# current_probe.net
KiCad netlist of a schematic drawn in EAGLE
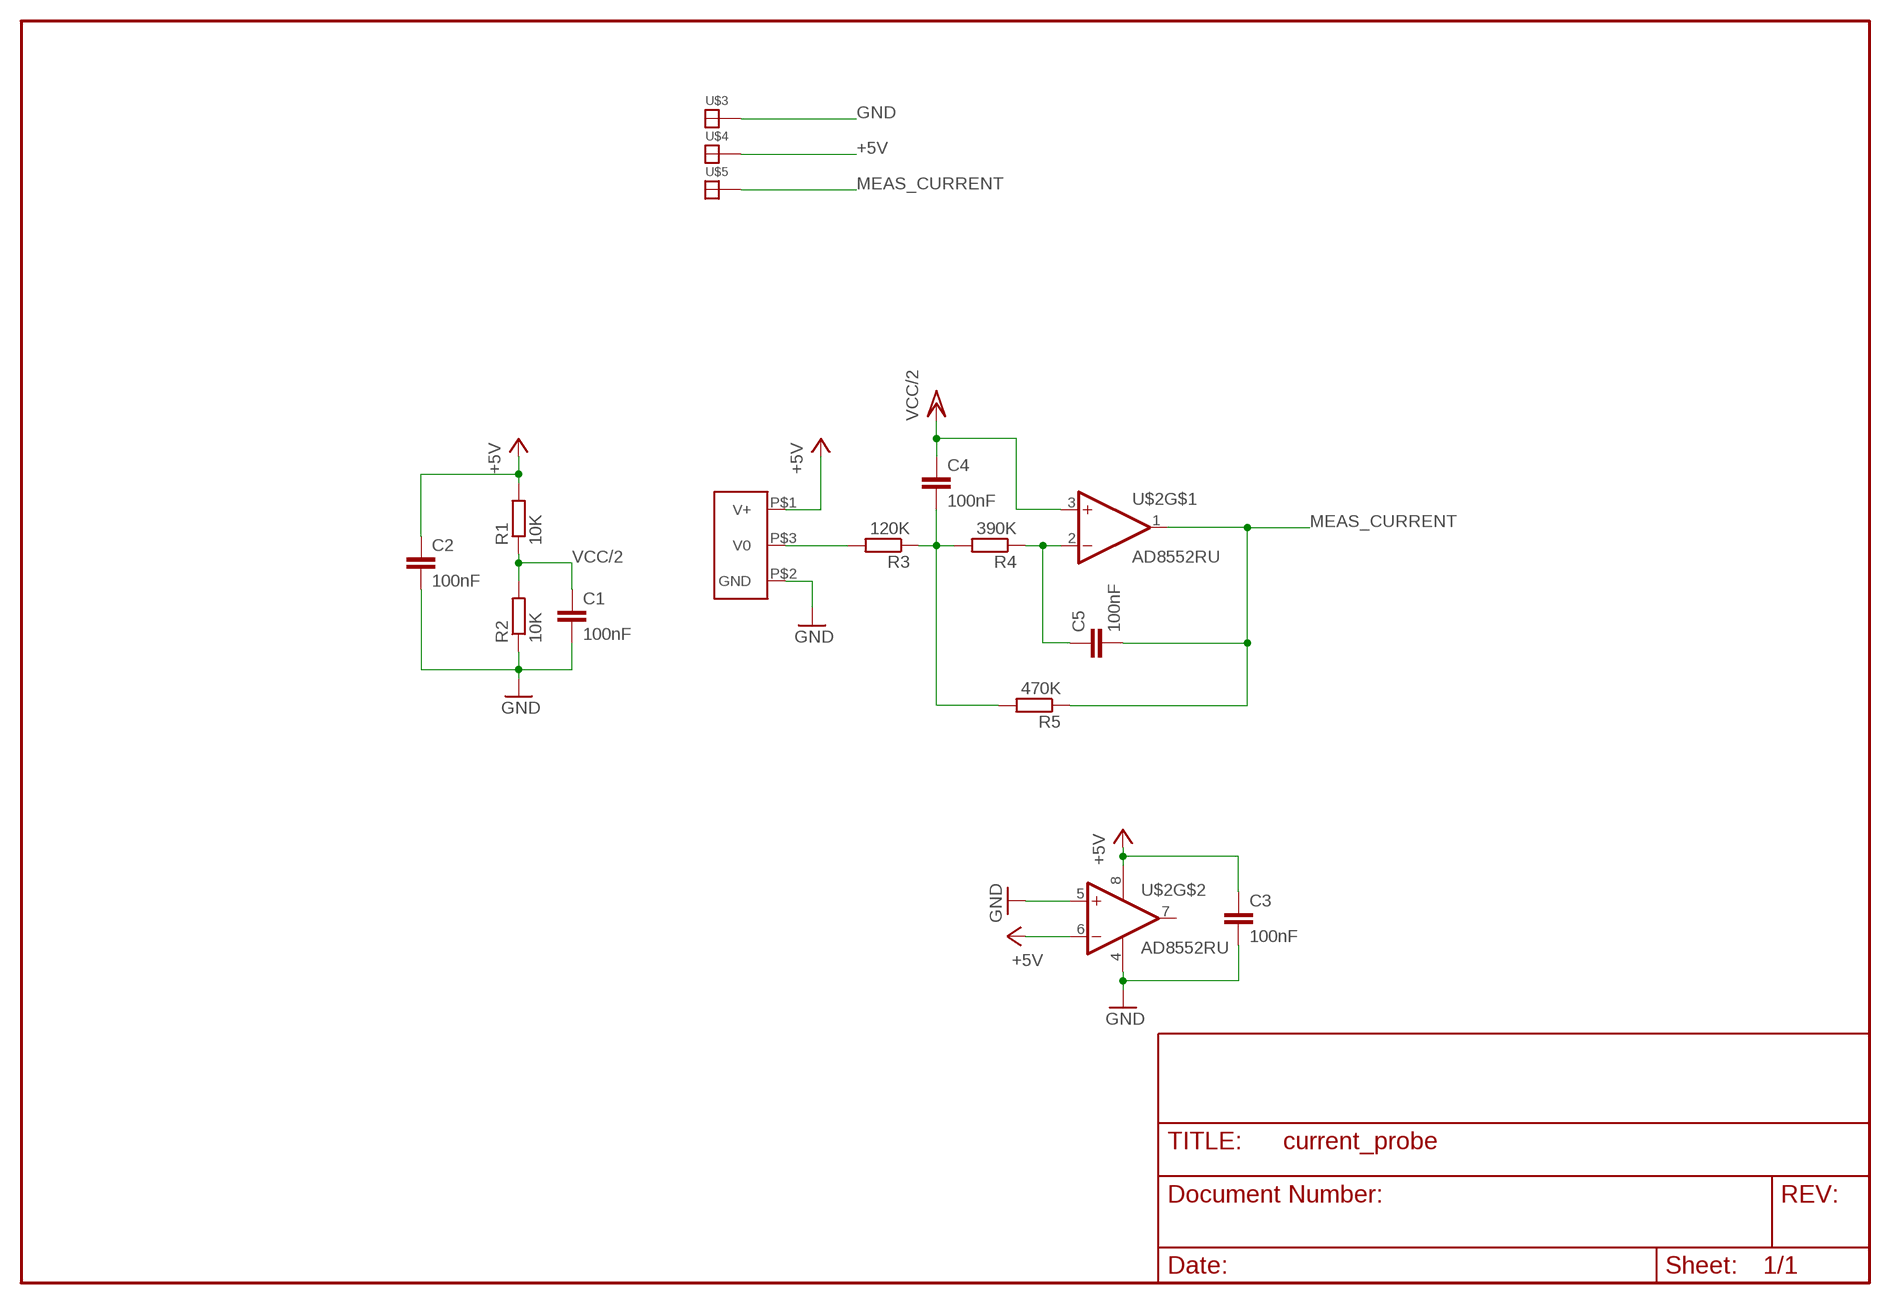
[diagram p0: schematic, sheet 1]

(export (version "E")
  (design (tool "Eeschema 10.0.6"))
  (components
    (comp (ref "C1")
      (value "100nF")
      (footprint "eagle-import:C0603K")
      (libsource (lib "eagle-import") (part "C-EUC0603K"))
    )
    (comp (ref "C2")
      (value "100nF")
      (footprint "eagle-import:C0603K")
      (libsource (lib "eagle-import") (part "C-EUC0603K"))
    )
    (comp (ref "C3")
      (value "100nF")
      (footprint "eagle-import:C0603K")
      (libsource (lib "eagle-import") (part "C-EUC0603K"))
    )
    (comp (ref "C4")
      (value "100nF")
      (footprint "eagle-import:C0603K")
      (libsource (lib "eagle-import") (part "C-EUC0603K"))
    )
    (comp (ref "C5")
      (value "100nF")
      (footprint "eagle-import:C0603K")
      (libsource (lib "eagle-import") (part "C-EUC0603K"))
    )
    (comp (ref "R1")
      (value "10K")
      (footprint "eagle-import:R0603")
      (libsource (lib "eagle-import") (part "R-EU_R0603"))
    )
    (comp (ref "R2")
      (value "10K")
      (footprint "eagle-import:R0603")
      (libsource (lib "eagle-import") (part "R-EU_R0603"))
    )
    (comp (ref "R3")
      (value "120K")
      (footprint "eagle-import:R0603")
      (libsource (lib "eagle-import") (part "R-EU_R0603"))
    )
    (comp (ref "R4")
      (value "390K")
      (footprint "eagle-import:R0603")
      (libsource (lib "eagle-import") (part "R-EU_R0603"))
    )
    (comp (ref "R5")
      (value "470K")
      (footprint "eagle-import:R0603")
      (libsource (lib "eagle-import") (part "R-EU_R0603"))
    )
    (comp (ref "U$1")
      (value "SS495S")
      (footprint "eagle-import:SS495SND")
      (libsource (lib "eagle-import") (part "SS495S"))
    )
    (comp (ref "U$2")
      (value "AD8552RU")
      (footprint "eagle-import:TSSOP8")
      (libsource (lib "eagle-import") (part "AD8552RU"))
    )
    (comp (ref "U$3")
      (value "SOLDER_PAD100_50")
      (footprint "eagle-import:SOLDER_PAD_100_50")
      (libsource (lib "eagle-import") (part "SOLDER_PAD100_50"))
    )
    (comp (ref "U$4")
      (value "SOLDER_PAD100_50")
      (footprint "eagle-import:SOLDER_PAD_100_50")
      (libsource (lib "eagle-import") (part "SOLDER_PAD100_50"))
    )
    (comp (ref "U$5")
      (value "SOLDER_PAD100_50")
      (footprint "eagle-import:SOLDER_PAD_100_50")
      (libsource (lib "eagle-import") (part "SOLDER_PAD100_50"))
    )
  )
  (nets
    (net (code "1") (name "+5V") (class "Default")
      (node (ref "C2") (pin "1") (pinfunction "1_1") (pintype "passive"))
      (node (ref "C3") (pin "1") (pinfunction "1_1") (pintype "passive"))
      (node (ref "R1") (pin "2") (pinfunction "2_2") (pintype "passive"))
      (node (ref "U$1") (pin "P$1") (pinfunction "V+_P$1") (pintype "bidirectional"))
      (node (ref "U$2") (pin "6") (pinfunction "-IN_6") (pintype "input"))
      (node (ref "U$2") (pin "8") (pinfunction "V+_8") (pintype "power_in"))
      (node (ref "U$4") (pin "P$1") (pinfunction "P$1_P$1") (pintype "bidirectional"))
    )
    (net (code "2") (name "/MEAS_CURRENT") (class "Default")
      (node (ref "C5") (pin "2") (pinfunction "2_2") (pintype "passive"))
      (node (ref "R5") (pin "1") (pinfunction "1_1") (pintype "passive"))
      (node (ref "U$2") (pin "1") (pinfunction "OUT_1") (pintype "output"))
      (node (ref "U$5") (pin "P$1") (pinfunction "P$1_P$1") (pintype "bidirectional"))
    )
    (net (code "3") (name "GND") (class "Default")
      (node (ref "C1") (pin "2") (pinfunction "2_2") (pintype "passive"))
      (node (ref "C2") (pin "2") (pinfunction "2_2") (pintype "passive"))
      (node (ref "C3") (pin "2") (pinfunction "2_2") (pintype "passive"))
      (node (ref "R2") (pin "1") (pinfunction "1_1") (pintype "passive"))
      (node (ref "U$1") (pin "P$2") (pinfunction "GND_P$2") (pintype "bidirectional"))
      (node (ref "U$2") (pin "4") (pinfunction "V-_4") (pintype "power_in"))
      (node (ref "U$2") (pin "5") (pinfunction "+IN_5") (pintype "input"))
      (node (ref "U$3") (pin "P$1") (pinfunction "P$1_P$1") (pintype "bidirectional"))
    )
    (net (code "4") (name "Net-(C4-Pad2)") (class "Default")
      (node (ref "C4") (pin "2") (pinfunction "2_2") (pintype "passive"))
      (node (ref "R3") (pin "1") (pinfunction "1_1") (pintype "passive"))
      (node (ref "R4") (pin "2") (pinfunction "2_2") (pintype "passive"))
      (node (ref "R5") (pin "2") (pinfunction "2_2") (pintype "passive"))
    )
    (net (code "5") (name "Net-(U$1-V0)") (class "Default")
      (node (ref "R3") (pin "2") (pinfunction "2_2") (pintype "passive"))
      (node (ref "U$1") (pin "P$3") (pinfunction "V0_P$3") (pintype "bidirectional"))
    )
    (net (code "6") (name "Net-(U$2A--IN)") (class "Default")
      (node (ref "C5") (pin "1") (pinfunction "1_1") (pintype "passive"))
      (node (ref "R4") (pin "1") (pinfunction "1_1") (pintype "passive"))
      (node (ref "U$2") (pin "2") (pinfunction "-IN_2") (pintype "input"))
    )
    (net (code "7") (name "VCC{slash}2") (class "Default")
      (node (ref "C1") (pin "1") (pinfunction "1_1") (pintype "passive"))
      (node (ref "C4") (pin "1") (pinfunction "1_1") (pintype "passive"))
      (node (ref "R1") (pin "1") (pinfunction "1_1") (pintype "passive"))
      (node (ref "R2") (pin "2") (pinfunction "2_2") (pintype "passive"))
      (node (ref "U$2") (pin "3") (pinfunction "+IN_3") (pintype "input"))
    )
    (net (code "8") (name "unconnected-(U$2B-OUT-Pad7)") (class "Default")
      (node (ref "U$2") (pin "7") (pinfunction "OUT_7") (pintype "output"))
    )
  )
)
